# Connectors.net
KiCad netlist of a schematic drawn in Altium Designer
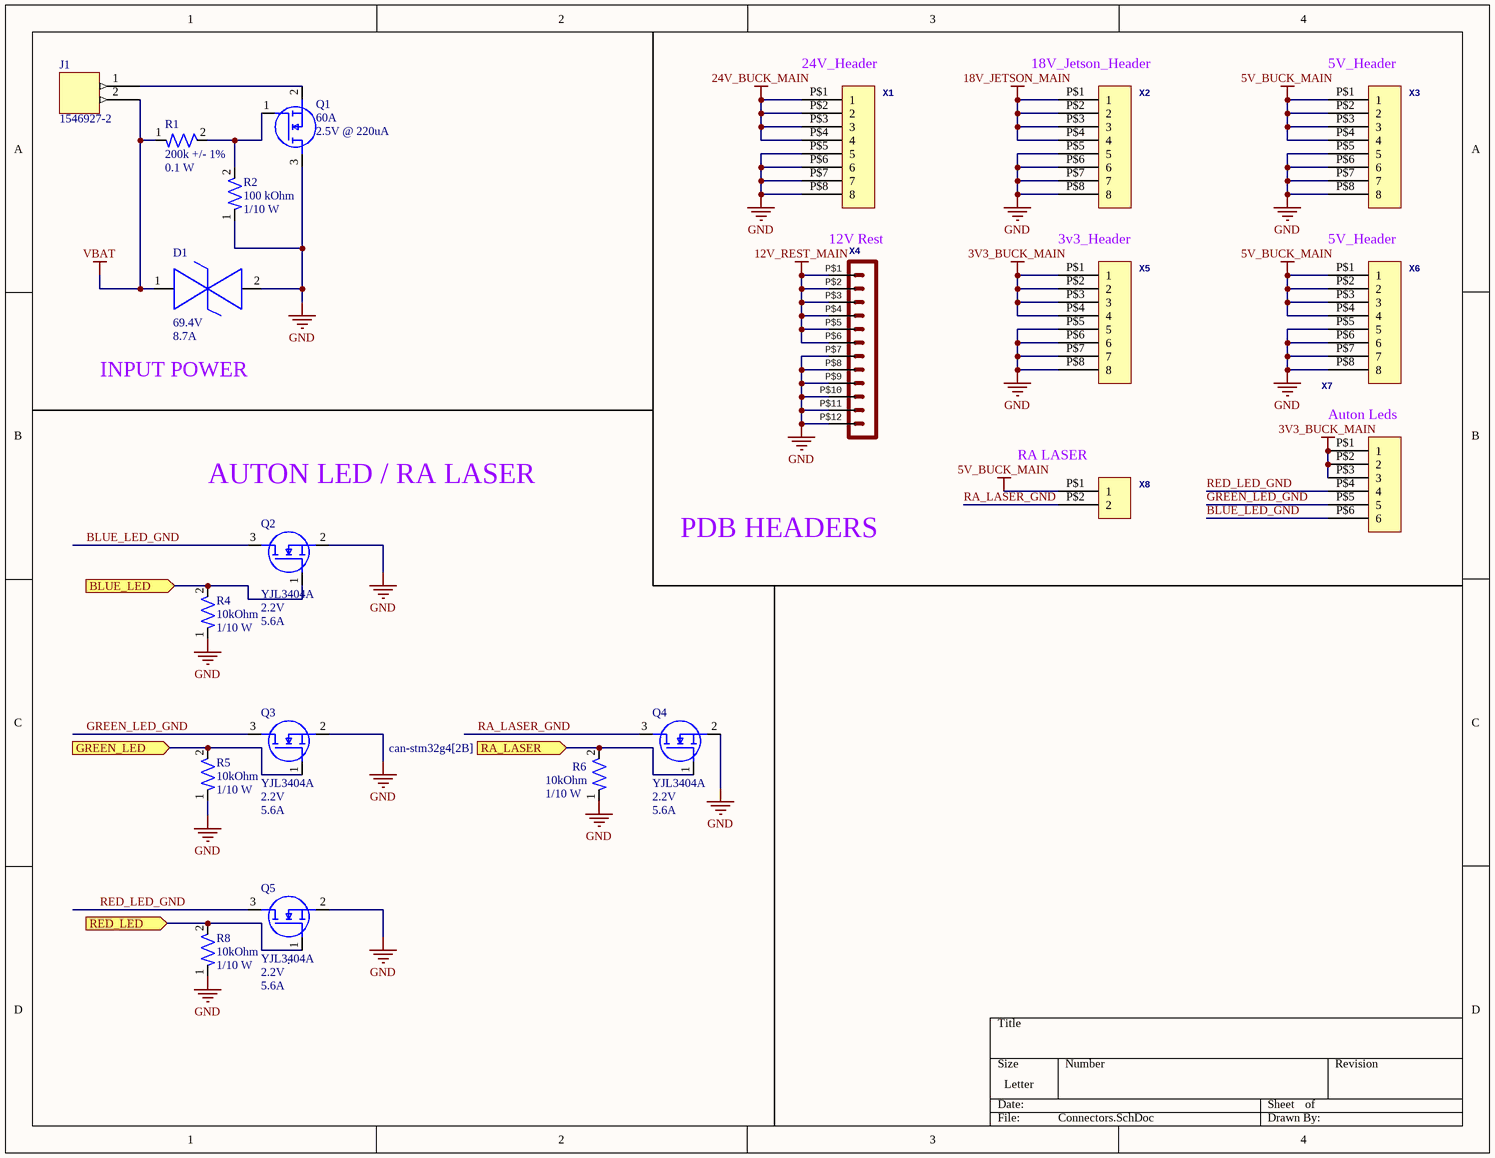
[diagram p0: Connectors.SchDoc]

(export (version "E")
  (design (tool "Eeschema 10.0.6"))
  (components
    (comp (ref "D1")
      (value "SMBJE43CAH")
      (footprint "DO-214AA (SMBJ)")
      (description "69.4V Clamp 8.7A Ipp Tvs Diode Surface Mount DO-214AA (SMBJ)")
      (fields (field (name "VCLAMP") "69.4V") (field (name "PEAK PULSER CURRENT") "8.7A"))
      (libsource (lib "MasterLib") (part "DIO-69.4V-0001"))
    )
    (comp (ref "J1")
      (value "1546927-2")
      (footprint "CONN-1546927-2")
      (libsource (lib "MasterLib") (part "CON-2POS-0003"))
    )
    (comp (ref "Q1")
      (value "TPH7R006PL,L1Q")
      (footprint "NMOS-8PowerVDFN")
      (description "N-Channel 60 V 60A (Tc) 81W (Tc) Surface Mount 8-SOP Advance (5x5)")
      (fields (field (name "DRAIN CURRENT") "60A") (field (name "VGS") "2.5V @ 220uA"))
      (libsource (lib "MasterLib") (part "NMOS-60A-0001"))
    )
    (comp (ref "Q2")
      (value "YJL3404A")
      (footprint "NMOS-SOT23-3")
      (description "N-Channel 30 V 5.6A (Ta) 1.2W (Ta) Surface Mount SOT-23")
      (fields (field (name "VGS(TH)") "2.2V") (field (name "DRAIN CURRENT") "5.6A"))
      (libsource (lib "MasterLib") (part "NMOS-5.6A-0001"))
    )
    (comp (ref "Q3")
      (value "YJL3404A")
      (footprint "NMOS-SOT23-3")
      (description "N-Channel 30 V 5.6A (Ta) 1.2W (Ta) Surface Mount SOT-23")
      (fields (field (name "VGS(TH)") "2.2V") (field (name "DRAIN CURRENT") "5.6A"))
      (libsource (lib "MasterLib") (part "NMOS-5.6A-0001"))
    )
    (comp (ref "Q4")
      (value "YJL3404A")
      (footprint "NMOS-SOT23-3")
      (description "N-Channel 30 V 5.6A (Ta) 1.2W (Ta) Surface Mount SOT-23")
      (fields (field (name "VGS(TH)") "2.2V") (field (name "DRAIN CURRENT") "5.6A"))
      (libsource (lib "MasterLib") (part "NMOS-5.6A-0001"))
    )
    (comp (ref "Q5")
      (value "YJL3404A")
      (footprint "NMOS-SOT23-3")
      (description "N-Channel 30 V 5.6A (Ta) 1.2W (Ta) Surface Mount SOT-23")
      (fields (field (name "VGS(TH)") "2.2V") (field (name "DRAIN CURRENT") "5.6A"))
      (libsource (lib "MasterLib") (part "NMOS-5.6A-0001"))
    )
    (comp (ref "R1")
      (value "ERJ-3EKF2003V")
      (footprint "RES-0603")
      (description "200 kOhms ±1% 0.1W, 1/10W Chip Resistor 0603 (1608 Metric) Automotive AEC-Q200 Thick Film")
      (fields
        (field (name "MANUFACTURER") "Panasonic Electronic Components")
        (field (name "RESISTANCE") "200k +/- 1%")
        (field (name "POWER RATING") "0.1 W")
      )
      (libsource (lib "MasterLib") (part "RES-200K-0001"))
    )
    (comp (ref "R2")
      (value "RC0603FR-07100KL")
      (footprint "RES-0603")
      (description "100 kOhms ±1% 0.1W, 1/10W Chip Resistor 0603 (1608 Metric) Moisture Resistant Thick Film")
      (fields
        (field (name "TOLERANCE") "+/- 1%")
        (field (name "RESISTANCE") "100 kOhm")
        (field (name "POWER") "1/10 W")
      )
      (libsource (lib "MasterLib") (part "RES-100K-0003"))
    )
    (comp (ref "R4")
      (value "RMCF0603ZT0R00")
      (footprint "RES-0603")
      (description "0 Ohms Jumper 0.1W, 1/10W Chip Resistor 0603 (1608 Metric) Automotive AEC-Q200 Thick Film")
      (fields (field (name "RESISTANCE") "10kOhm") (field (name "POWER") "1/10 W"))
      (libsource (lib "MasterLib") (part "RES-0-0001"))
    )
    (comp (ref "R5")
      (value "RMCF0603ZT0R00")
      (footprint "RES-0603")
      (description "0 Ohms Jumper 0.1W, 1/10W Chip Resistor 0603 (1608 Metric) Automotive AEC-Q200 Thick Film")
      (fields (field (name "RESISTANCE") "10kOhm") (field (name "POWER") "1/10 W"))
      (libsource (lib "MasterLib") (part "RES-0-0001"))
    )
    (comp (ref "R6")
      (value "RMCF0603ZT0R00")
      (footprint "RES-0603")
      (description "0 Ohms Jumper 0.1W, 1/10W Chip Resistor 0603 (1608 Metric) Automotive AEC-Q200 Thick Film")
      (fields (field (name "RESISTANCE") "10kOhm") (field (name "POWER") "1/10 W"))
      (libsource (lib "MasterLib") (part "RES-0-0001"))
    )
    (comp (ref "R8")
      (value "RMCF0603ZT0R00")
      (footprint "RES-0603")
      (description "0 Ohms Jumper 0.1W, 1/10W Chip Resistor 0603 (1608 Metric) Automotive AEC-Q200 Thick Film")
      (fields (field (name "RESISTANCE") "10kOhm") (field (name "POWER") "1/10 W"))
      (libsource (lib "MasterLib") (part "RES-0-0001"))
    )
    (comp (ref "X1")
      (value "Molex 43045-0812")
      (footprint "43045-0812")
      (libsource (lib "Molex Microfit") (part "Micro-Fit Molex 8 Pin 2 Row Vertical"))
    )
    (comp (ref "X2")
      (value "Molex 43045-0812")
      (footprint "43045-0812")
      (libsource (lib "Molex Microfit") (part "Micro-Fit Molex 8 Pin 2 Row Vertical"))
    )
    (comp (ref "X3")
      (value "Molex 43045-0812")
      (footprint "43045-0812")
      (libsource (lib "Molex Microfit") (part "Micro-Fit Molex 8 Pin 2 Row Vertical"))
    )
    (comp (ref "X4")
      (value "Molex - Micro-Fit 3.0 Series connector,  3.00mm (0.118\") pitch header, 12 positions.")
      (footprint "43045-1212")
      (libsource (lib "Molex Microfit") (part "HEADER_POS12_?43045-1212"))
    )
    (comp (ref "X5")
      (value "Molex 43045-0812")
      (footprint "43045-0812")
      (libsource (lib "Molex Microfit") (part "Micro-Fit Molex 8 Pin 2 Row Vertical"))
    )
    (comp (ref "X6")
      (value "Molex 43045-0812")
      (footprint "43045-0812")
      (libsource (lib "Molex Microfit") (part "Micro-Fit Molex 8 Pin 2 Row Vertical"))
    )
    (comp (ref "X7")
      (value "Molex 43045-0612")
      (footprint "43045-0612")
      (libsource (lib "Molex Microfit") (part "Micro-Fit Molex 6 Pin 2 Row Vertical"))
    )
    (comp (ref "X8")
      (value "Molex 43650-0215")
      (footprint "43650-0215")
      (libsource (lib "Molex Microfit") (part "Micro-Fit Molex 2 Pin Vertical"))
    )
  )
  (nets
    (net (code "1") (name "/BLUE_LED") (class "Default")
      (node (ref "Q2") (pin "1") (pinfunction "G_1") (pintype "passive"))
      (node (ref "R4") (pin "2") (pinfunction "2_2") (pintype "passive"))
    )
    (net (code "2") (name "/BLUE_LED_GND") (class "Default")
      (node (ref "Q2") (pin "3") (pinfunction "D_3") (pintype "passive"))
      (node (ref "X7") (pin "P$6") (pinfunction "6_P$6") (pintype "passive"))
    )
    (net (code "3") (name "/GREEN_LED") (class "Default")
      (node (ref "Q3") (pin "1") (pinfunction "G_1") (pintype "passive"))
      (node (ref "R5") (pin "2") (pinfunction "2_2") (pintype "passive"))
    )
    (net (code "4") (name "/GREEN_LED_GND") (class "Default")
      (node (ref "Q3") (pin "3") (pinfunction "D_3") (pintype "passive"))
      (node (ref "X7") (pin "P$5") (pinfunction "5_P$5") (pintype "passive"))
    )
    (net (code "5") (name "/RA_LASER") (class "Default")
      (node (ref "Q4") (pin "1") (pinfunction "G_1") (pintype "passive"))
      (node (ref "R6") (pin "2") (pinfunction "2_2") (pintype "passive"))
    )
    (net (code "6") (name "/RA_LASER_GND") (class "Default")
      (node (ref "Q4") (pin "3") (pinfunction "D_3") (pintype "passive"))
      (node (ref "X8") (pin "P$2") (pinfunction "2_P$2") (pintype "passive"))
    )
    (net (code "7") (name "/RED_LED") (class "Default")
      (node (ref "Q5") (pin "1") (pinfunction "G_1") (pintype "passive"))
      (node (ref "R8") (pin "2") (pinfunction "2_2") (pintype "passive"))
    )
    (net (code "8") (name "/RED_LED_GND") (class "Default")
      (node (ref "Q5") (pin "3") (pinfunction "D_3") (pintype "passive"))
      (node (ref "X7") (pin "P$4") (pinfunction "4_P$4") (pintype "passive"))
    )
    (net (code "9") (name "3V3_BUCK_MAIN") (class "Default")
      (node (ref "X5") (pin "P$1") (pinfunction "1_P$1") (pintype "passive"))
      (node (ref "X5") (pin "P$2") (pinfunction "2_P$2") (pintype "passive"))
      (node (ref "X5") (pin "P$3") (pinfunction "3_P$3") (pintype "passive"))
      (node (ref "X5") (pin "P$4") (pinfunction "4_P$4") (pintype "passive"))
      (node (ref "X7") (pin "P$1") (pinfunction "1_P$1") (pintype "passive"))
      (node (ref "X7") (pin "P$2") (pinfunction "2_P$2") (pintype "passive"))
      (node (ref "X7") (pin "P$3") (pinfunction "3_P$3") (pintype "passive"))
    )
    (net (code "10") (name "5V_BUCK_MAIN") (class "Default")
      (node (ref "X3") (pin "P$1") (pinfunction "1_P$1") (pintype "passive"))
      (node (ref "X3") (pin "P$2") (pinfunction "2_P$2") (pintype "passive"))
      (node (ref "X3") (pin "P$3") (pinfunction "3_P$3") (pintype "passive"))
      (node (ref "X3") (pin "P$4") (pinfunction "4_P$4") (pintype "passive"))
      (node (ref "X6") (pin "P$1") (pinfunction "1_P$1") (pintype "passive"))
      (node (ref "X6") (pin "P$2") (pinfunction "2_P$2") (pintype "passive"))
      (node (ref "X6") (pin "P$3") (pinfunction "3_P$3") (pintype "passive"))
      (node (ref "X6") (pin "P$4") (pinfunction "4_P$4") (pintype "passive"))
      (node (ref "X8") (pin "P$1") (pinfunction "1_P$1") (pintype "passive"))
    )
    (net (code "11") (name "12V_REST_MAIN") (class "Default")
      (node (ref "X4") (pin "P$1") (pinfunction "1_P$1") (pintype "passive"))
      (node (ref "X4") (pin "P$2") (pinfunction "2_P$2") (pintype "passive"))
      (node (ref "X4") (pin "P$3") (pinfunction "3_P$3") (pintype "passive"))
      (node (ref "X4") (pin "P$4") (pinfunction "4_P$4") (pintype "passive"))
      (node (ref "X4") (pin "P$5") (pinfunction "5_P$5") (pintype "passive"))
      (node (ref "X4") (pin "P$6") (pinfunction "6_P$6") (pintype "passive"))
    )
    (net (code "12") (name "18V_JETSON_MAIN") (class "Default")
      (node (ref "X2") (pin "P$1") (pinfunction "1_P$1") (pintype "passive"))
      (node (ref "X2") (pin "P$2") (pinfunction "2_P$2") (pintype "passive"))
      (node (ref "X2") (pin "P$3") (pinfunction "3_P$3") (pintype "passive"))
      (node (ref "X2") (pin "P$4") (pinfunction "4_P$4") (pintype "passive"))
    )
    (net (code "13") (name "24V_BUCK_MAIN") (class "Default")
      (node (ref "X1") (pin "P$1") (pinfunction "1_P$1") (pintype "passive"))
      (node (ref "X1") (pin "P$2") (pinfunction "2_P$2") (pintype "passive"))
      (node (ref "X1") (pin "P$3") (pinfunction "3_P$3") (pintype "passive"))
      (node (ref "X1") (pin "P$4") (pinfunction "4_P$4") (pintype "passive"))
    )
    (net (code "14") (name "GND") (class "Default")
      (node (ref "D1") (pin "2") (pintype "passive"))
      (node (ref "Q1") (pin "3") (pinfunction "D_3") (pintype "passive"))
      (node (ref "Q2") (pin "2") (pinfunction "S_2") (pintype "passive"))
      (node (ref "Q3") (pin "2") (pinfunction "S_2") (pintype "passive"))
      (node (ref "Q4") (pin "2") (pinfunction "S_2") (pintype "passive"))
      (node (ref "Q5") (pin "2") (pinfunction "S_2") (pintype "passive"))
      (node (ref "R2") (pin "1") (pinfunction "1_1") (pintype "passive"))
      (node (ref "R4") (pin "1") (pinfunction "1_1") (pintype "passive"))
      (node (ref "R5") (pin "1") (pinfunction "1_1") (pintype "passive"))
      (node (ref "R6") (pin "1") (pinfunction "1_1") (pintype "passive"))
      (node (ref "R8") (pin "1") (pinfunction "1_1") (pintype "passive"))
      (node (ref "X1") (pin "P$5") (pinfunction "5_P$5") (pintype "passive"))
      (node (ref "X1") (pin "P$6") (pinfunction "6_P$6") (pintype "passive"))
      (node (ref "X1") (pin "P$7") (pinfunction "7_P$7") (pintype "passive"))
      (node (ref "X1") (pin "P$8") (pinfunction "8_P$8") (pintype "passive"))
      (node (ref "X2") (pin "P$5") (pinfunction "5_P$5") (pintype "passive"))
      (node (ref "X2") (pin "P$6") (pinfunction "6_P$6") (pintype "passive"))
      (node (ref "X2") (pin "P$7") (pinfunction "7_P$7") (pintype "passive"))
      (node (ref "X2") (pin "P$8") (pinfunction "8_P$8") (pintype "passive"))
      (node (ref "X3") (pin "P$5") (pinfunction "5_P$5") (pintype "passive"))
      (node (ref "X3") (pin "P$6") (pinfunction "6_P$6") (pintype "passive"))
      (node (ref "X3") (pin "P$7") (pinfunction "7_P$7") (pintype "passive"))
      (node (ref "X3") (pin "P$8") (pinfunction "8_P$8") (pintype "passive"))
      (node (ref "X4") (pin "P$10") (pinfunction "10_P$10") (pintype "passive"))
      (node (ref "X4") (pin "P$11") (pinfunction "11_P$11") (pintype "passive"))
      (node (ref "X4") (pin "P$12") (pinfunction "12_P$12") (pintype "passive"))
      (node (ref "X4") (pin "P$7") (pinfunction "7_P$7") (pintype "passive"))
      (node (ref "X4") (pin "P$8") (pinfunction "8_P$8") (pintype "passive"))
      (node (ref "X4") (pin "P$9") (pinfunction "9_P$9") (pintype "passive"))
      (node (ref "X5") (pin "P$5") (pinfunction "5_P$5") (pintype "passive"))
      (node (ref "X5") (pin "P$6") (pinfunction "6_P$6") (pintype "passive"))
      (node (ref "X5") (pin "P$7") (pinfunction "7_P$7") (pintype "passive"))
      (node (ref "X5") (pin "P$8") (pinfunction "8_P$8") (pintype "passive"))
      (node (ref "X6") (pin "P$5") (pinfunction "5_P$5") (pintype "passive"))
      (node (ref "X6") (pin "P$6") (pinfunction "6_P$6") (pintype "passive"))
      (node (ref "X6") (pin "P$7") (pinfunction "7_P$7") (pintype "passive"))
      (node (ref "X6") (pin "P$8") (pinfunction "8_P$8") (pintype "passive"))
    )
    (net (code "15") (name "Net-(Q1-G)") (class "Default")
      (node (ref "Q1") (pin "1") (pinfunction "G_1") (pintype "passive"))
      (node (ref "R1") (pin "2") (pinfunction "2_2") (pintype "passive"))
      (node (ref "R2") (pin "2") (pinfunction "2_2") (pintype "passive"))
    )
    (net (code "16") (name "Net-(Q1-S)") (class "Default")
      (node (ref "J1") (pin "1") (pintype "output"))
      (node (ref "Q1") (pin "2") (pinfunction "S_2") (pintype "passive"))
    )
    (net (code "17") (name "VBAT") (class "Default")
      (node (ref "D1") (pin "1") (pintype "passive"))
      (node (ref "J1") (pin "2") (pintype "output"))
      (node (ref "R1") (pin "1") (pinfunction "1_1") (pintype "passive"))
    )
  )
)
